# Isolator.net
KiCad netlist of a schematic drawn in EAGLE
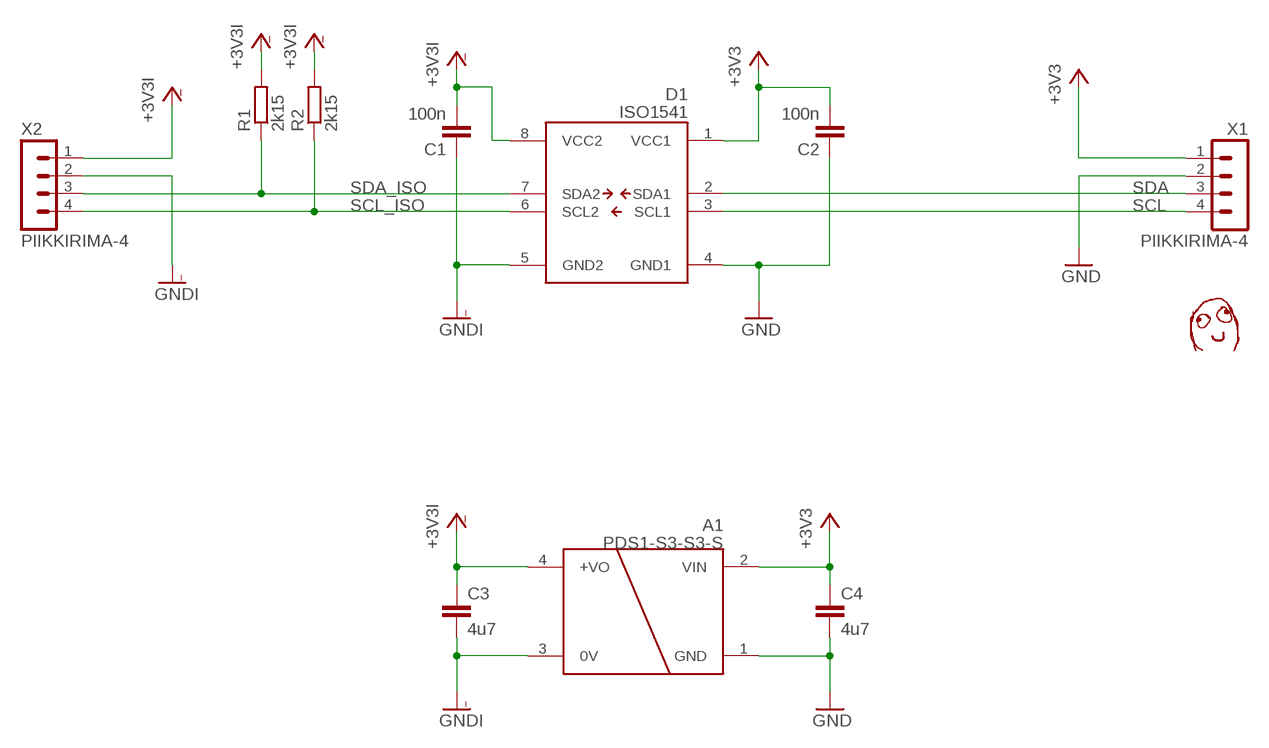
[diagram p0: schematic, sheet 1]

(export (version "E")
  (design (tool "Eeschema 10.0.6"))
  (components
    (comp (ref "A1")
      (value "PDS1-S3-S3-S")
      (footprint "eagle-import:DCDC_SIP4")
      (libsource (lib "eagle-import") (part "PDS1--SS3-S3"))
    )
    (comp (ref "C1")
      (value "100n")
      (footprint "eagle-import:C0603")
      (libsource (lib "eagle-import") (part "C-EUC0603"))
    )
    (comp (ref "C2")
      (value "100n")
      (footprint "eagle-import:C0603")
      (libsource (lib "eagle-import") (part "C-EUC0603"))
    )
    (comp (ref "C3")
      (value "4u7")
      (footprint "eagle-import:C0805")
      (libsource (lib "eagle-import") (part "C-EUC0805"))
    )
    (comp (ref "C4")
      (value "4u7")
      (footprint "eagle-import:C0805")
      (libsource (lib "eagle-import") (part "C-EUC0805"))
    )
    (comp (ref "D1")
      (value "ISO1541")
      (footprint "eagle-import:SOIC8-N_MC")
      (libsource (lib "eagle-import") (part "ISO1541"))
    )
    (comp (ref "R1")
      (value "2k15")
      (footprint "eagle-import:R0603")
      (libsource (lib "eagle-import") (part "R-EU_R0603"))
    )
    (comp (ref "R2")
      (value "2k15")
      (footprint "eagle-import:R0603")
      (libsource (lib "eagle-import") (part "R-EU_R0603"))
    )
    (comp (ref "U$1")
      (value "DAFUG")
      (footprint "eagle-import:DAFUG")
      (libsource (lib "eagle-import") (part "DAFUG"))
    )
    (comp (ref "X1")
      (value "PIIKKIRIMA-4")
      (footprint "eagle-import:PIIKKIRIMA-4")
      (libsource (lib "eagle-import") (part "PIIKKIRIMA-4"))
    )
    (comp (ref "X2")
      (value "PIIKKIRIMA-4")
      (footprint "eagle-import:PIIKKIRIMA-4")
      (libsource (lib "eagle-import") (part "PIIKKIRIMA-4"))
    )
  )
  (nets
    (net (code "1") (name "+3V3") (class "Default")
      (node (ref "A1") (pin "2") (pinfunction "VIN_2") (pintype "bidirectional"))
      (node (ref "C2") (pin "2") (pinfunction "2_2") (pintype "passive"))
      (node (ref "C4") (pin "1") (pinfunction "1_1") (pintype "passive"))
      (node (ref "D1") (pin "1") (pinfunction "VCC1_1") (pintype "bidirectional"))
      (node (ref "X1") (pin "1") (pinfunction "1_1") (pintype "passive"))
    )
    (net (code "2") (name "+3V3I") (class "Default")
      (node (ref "A1") (pin "4") (pinfunction "+VO_4") (pintype "bidirectional"))
      (node (ref "C1") (pin "2") (pinfunction "2_2") (pintype "passive"))
      (node (ref "C3") (pin "1") (pinfunction "1_1") (pintype "passive"))
      (node (ref "D1") (pin "8") (pinfunction "VCC2_8") (pintype "bidirectional"))
      (node (ref "R1") (pin "2") (pinfunction "2_2") (pintype "passive"))
      (node (ref "R2") (pin "2") (pinfunction "2_2") (pintype "passive"))
      (node (ref "X2") (pin "1") (pinfunction "1_1") (pintype "passive"))
    )
    (net (code "3") (name "/SCL") (class "Default")
      (node (ref "D1") (pin "3") (pinfunction "SCL1_3") (pintype "bidirectional"))
      (node (ref "X1") (pin "4") (pinfunction "4_4") (pintype "passive"))
    )
    (net (code "4") (name "/SCL_ISO") (class "Default")
      (node (ref "D1") (pin "6") (pinfunction "SCL2_6") (pintype "bidirectional"))
      (node (ref "R2") (pin "1") (pinfunction "1_1") (pintype "passive"))
      (node (ref "X2") (pin "4") (pinfunction "4_4") (pintype "passive"))
    )
    (net (code "5") (name "/SDA") (class "Default")
      (node (ref "D1") (pin "2") (pinfunction "SDA1_2") (pintype "bidirectional"))
      (node (ref "X1") (pin "3") (pinfunction "3_3") (pintype "passive"))
    )
    (net (code "6") (name "/SDA_ISO") (class "Default")
      (node (ref "D1") (pin "7") (pinfunction "SDA2_7") (pintype "bidirectional"))
      (node (ref "R1") (pin "1") (pinfunction "1_1") (pintype "passive"))
      (node (ref "X2") (pin "3") (pinfunction "3_3") (pintype "passive"))
    )
    (net (code "7") (name "GND") (class "Default")
      (node (ref "A1") (pin "1") (pinfunction "GND_1") (pintype "bidirectional"))
      (node (ref "C2") (pin "1") (pinfunction "1_1") (pintype "passive"))
      (node (ref "C4") (pin "2") (pinfunction "2_2") (pintype "passive"))
      (node (ref "D1") (pin "4") (pinfunction "GND1_4") (pintype "bidirectional"))
      (node (ref "X1") (pin "2") (pinfunction "2_2") (pintype "passive"))
    )
    (net (code "8") (name "GNDI") (class "Default")
      (node (ref "A1") (pin "3") (pinfunction "0V_3") (pintype "bidirectional"))
      (node (ref "C1") (pin "1") (pinfunction "1_1") (pintype "passive"))
      (node (ref "C3") (pin "2") (pinfunction "2_2") (pintype "passive"))
      (node (ref "D1") (pin "5") (pinfunction "GND2_5") (pintype "bidirectional"))
      (node (ref "X2") (pin "2") (pinfunction "2_2") (pintype "passive"))
    )
  )
)
